# RS-485.net
KiCad netlist of a schematic drawn in Altium Designer
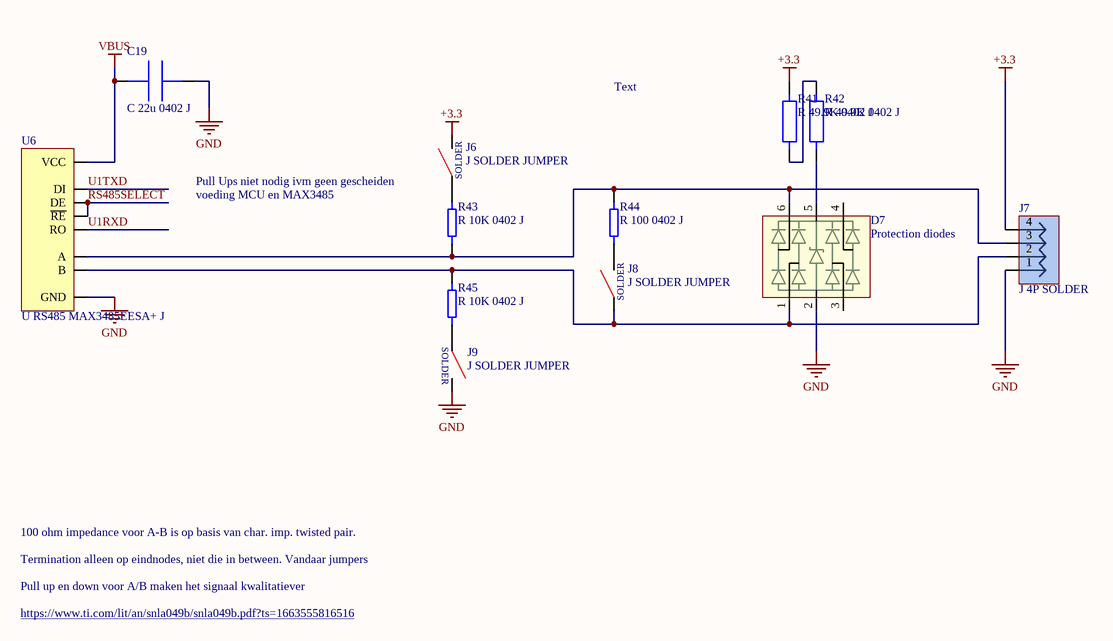
[diagram p0: RS-485.SchDoc]

(export (version "E")
  (design (tool "Eeschema 10.0.6"))
  (components
    (comp (ref "C19")
      (value "C 22u 0402 J")
      (footprint "C0402")
      (description "Multi-Layer Ceramic Capacitor 22uF 2.5VDC X6S 20% 0402 Paper T/R GRM155C80E226ME11D")
      (fields
        (field (name "MANUFACTURER") "Murata")
        (field (name "MANUFACTURER PART NUMBER") "GRM155C80E226ME11D")
      )
      (libsource (lib "Schlib1") (part "C 22u 0402 J"))
    )
    (comp (ref "D7")
      (value "Protection diodes")
      (footprint "SOT23-SRV05")
      (description "SEMTECH - SRV05-4.TCT - ESD Protection Device, TVS, 17.5 V, SOT-23, 6 Pins, 5 V, 300 W")
      (fields (field (name "MANUFACTURER") "Semtech") (field (name "MANUFACTURER PART NUMBER") "SRV05-4.TCT"))
      (libsource (lib "Schlib1") (part "D SRV05-4.TCT"))
    )
    (comp (ref "J6")
      (value "J SOLDER JUMPER")
      (footprint "SOLDER_JUMPER")
      (libsource (lib "Schlib1") (part "J SOLDER JUMPER"))
    )
    (comp (ref "J7")
      (value "J 4P SOLDER")
      (footprint "4P SOLDER BRIDGE")
      (libsource (lib "Schlib1") (part "J 4P SOLDER"))
    )
    (comp (ref "J8")
      (value "J SOLDER JUMPER")
      (footprint "SOLDER_JUMPER")
      (description "No-BOM solder jumper (test method)")
      (libsource (lib "Schlib1") (part "J SOLDER JUMPER"))
    )
    (comp (ref "J9")
      (value "J SOLDER JUMPER")
      (footprint "SOLDER_JUMPER")
      (libsource (lib "Schlib1") (part "J SOLDER JUMPER"))
    )
    (comp (ref "R41")
      (value "R 49.9K 0402 J")
      (footprint "R0402")
      (fields
        (field (name "MANUFACTURER") "Yageo")
        (field (name "MANUFACTURER PART NUMBER") "RC0402FR-0749K9L")
        (field (name "TOLERANCE") "1%")
      )
      (libsource (lib "Schlib1") (part "R 49.9K 0402 J"))
    )
    (comp (ref "R42")
      (value "R 49.9K 0402 J")
      (footprint "R0402")
      (fields
        (field (name "MANUFACTURER") "Yageo")
        (field (name "MANUFACTURER PART NUMBER") "RC0402FR-0749K9L")
        (field (name "TOLERANCE") "1%")
      )
      (libsource (lib "Schlib1") (part "R 49.9K 0402 J"))
    )
    (comp (ref "R43")
      (value "R 10K 0402 J")
      (footprint "R0402")
      (description "Res Thick Film 0402 10K Ohm 1% 0.063W(1/16W) ±100ppm/C Pad SMD Automotive T/R AC0402FR-0710KL")
      (fields
        (field (name "MANUFACTURER") "Yageo")
        (field (name "MANUFACTURER PART NUMBER") "AC0402FR-0710KL")
      )
      (libsource (lib "Schlib1") (part "R 10K 0402 J"))
    )
    (comp (ref "R44")
      (value "R 100 0402 J")
      (footprint "R0402")
      (fields
        (field (name "MANUFACTURER") "Yageo")
        (field (name "MANUFACTURER PART NUMBER") "RC0402JR-07100RL")
        (field (name "TOLERANCE") "5%")
      )
      (libsource (lib "Schlib1") (part "R 100 0402 J"))
    )
    (comp (ref "R45")
      (value "R 10K 0402 J")
      (footprint "R0402")
      (description "Res Thick Film 0402 10K Ohm 1% 0.063W(1/16W) ±100ppm/C Pad SMD Automotive T/R AC0402FR-0710KL")
      (fields
        (field (name "MANUFACTURER") "Yageo")
        (field (name "MANUFACTURER PART NUMBER") "AC0402FR-0710KL")
      )
      (libsource (lib "Schlib1") (part "R 10K 0402 J"))
    )
    (comp (ref "U6")
      (value "U RS485 MAX3485EESA+ J")
      (footprint "SOIC8 - V2")
      (description "Single Transmitter/Receiver RS-422/RS-485 8-Pin SOIC N")
      (fields (field (name "MANUFACTURER") "Maxim") (field (name "MANUFACTURER PART NUMBER") "MAX3485EESA+"))
      (libsource (lib "Schlib1") (part "U RS485 MAX3485EESA+ J"))
    )
  )
  (nets
    (net (code "1") (name "+3.3") (class "Default")
      (node (ref "J6") (pin "2") (pinfunction "2_2") (pintype "passive"))
      (node (ref "J7") (pin "4") (pinfunction "SEL_4") (pintype "passive"))
      (node (ref "R41") (pin "2") (pinfunction "2_2") (pintype "passive"))
    )
    (net (code "2") (name "/RS485SELECT") (class "Default")
      (node (ref "U6") (pin "2") (pinfunction "~{RE}_2") (pintype "passive"))
      (node (ref "U6") (pin "3") (pinfunction "DE_3") (pintype "passive"))
    )
    (net (code "3") (name "/U1RXD") (class "Default")
      (node (ref "U6") (pin "1") (pinfunction "RO_1") (pintype "passive"))
    )
    (net (code "4") (name "/U1TXD") (class "Default")
      (node (ref "U6") (pin "4") (pinfunction "DI_4") (pintype "passive"))
    )
    (net (code "5") (name "GND") (class "Default")
      (node (ref "C19") (pin "2") (pinfunction "2_2") (pintype "passive"))
      (node (ref "D7") (pin "2") (pinfunction "2_2") (pintype "passive"))
      (node (ref "J7") (pin "1") (pinfunction "VDD_1") (pintype "passive"))
      (node (ref "J9") (pin "2") (pinfunction "2_2") (pintype "passive"))
      (node (ref "U6") (pin "5") (pinfunction "GND_5") (pintype "passive"))
    )
    (net (code "6") (name "Net-(D7-Pad5)") (class "Default")
      (node (ref "D7") (pin "5") (pinfunction "5_5") (pintype "passive"))
      (node (ref "R42") (pin "1") (pinfunction "1_1") (pintype "passive"))
    )
    (net (code "7") (name "Net-(J6-Pad1)") (class "Default")
      (node (ref "J6") (pin "1") (pinfunction "1_1") (pintype "passive"))
      (node (ref "R43") (pin "2") (pinfunction "2_2") (pintype "passive"))
    )
    (net (code "8") (name "Net-(J7-SCL)") (class "Default")
      (node (ref "D7") (pin "6") (pinfunction "6_6") (pintype "passive"))
      (node (ref "J7") (pin "3") (pinfunction "SCL_3") (pintype "passive"))
      (node (ref "R43") (pin "1") (pinfunction "1_1") (pintype "passive"))
      (node (ref "R44") (pin "2") (pinfunction "2_2") (pintype "passive"))
      (node (ref "U6") (pin "6") (pinfunction "A_6") (pintype "passive"))
    )
    (net (code "9") (name "Net-(J7-SDA)") (class "Default")
      (node (ref "D7") (pin "1") (pinfunction "1_1") (pintype "passive"))
      (node (ref "J7") (pin "2") (pinfunction "SDA_2") (pintype "passive"))
      (node (ref "J8") (pin "1") (pinfunction "1_1") (pintype "passive"))
      (node (ref "R45") (pin "2") (pinfunction "2_2") (pintype "passive"))
      (node (ref "U6") (pin "7") (pinfunction "B_7") (pintype "passive"))
    )
    (net (code "10") (name "Net-(J8-Pad2)") (class "Default")
      (node (ref "J8") (pin "2") (pinfunction "2_2") (pintype "passive"))
      (node (ref "R44") (pin "1") (pinfunction "1_1") (pintype "passive"))
    )
    (net (code "11") (name "Net-(J9-Pad1)") (class "Default")
      (node (ref "J9") (pin "1") (pinfunction "1_1") (pintype "passive"))
      (node (ref "R45") (pin "1") (pinfunction "1_1") (pintype "passive"))
    )
    (net (code "12") (name "Net-(R41-Pad1)") (class "Default")
      (node (ref "R41") (pin "1") (pinfunction "1_1") (pintype "passive"))
      (node (ref "R42") (pin "2") (pinfunction "2_2") (pintype "passive"))
    )
    (net (code "13") (name "VBUS") (class "Default")
      (node (ref "C19") (pin "1") (pinfunction "1_1") (pintype "passive"))
      (node (ref "U6") (pin "8") (pinfunction "VCC_8") (pintype "passive"))
    )
    (net (code "14") (name "unconnected-(D7-Pad3)") (class "Default")
      (node (ref "D7") (pin "3") (pinfunction "3_3") (pintype "passive"))
    )
    (net (code "15") (name "unconnected-(D7-Pad4)") (class "Default")
      (node (ref "D7") (pin "4") (pinfunction "4_4") (pintype "passive"))
    )
  )
)
